# mcu.net
KiCad netlist of a schematic drawn in EAGLE
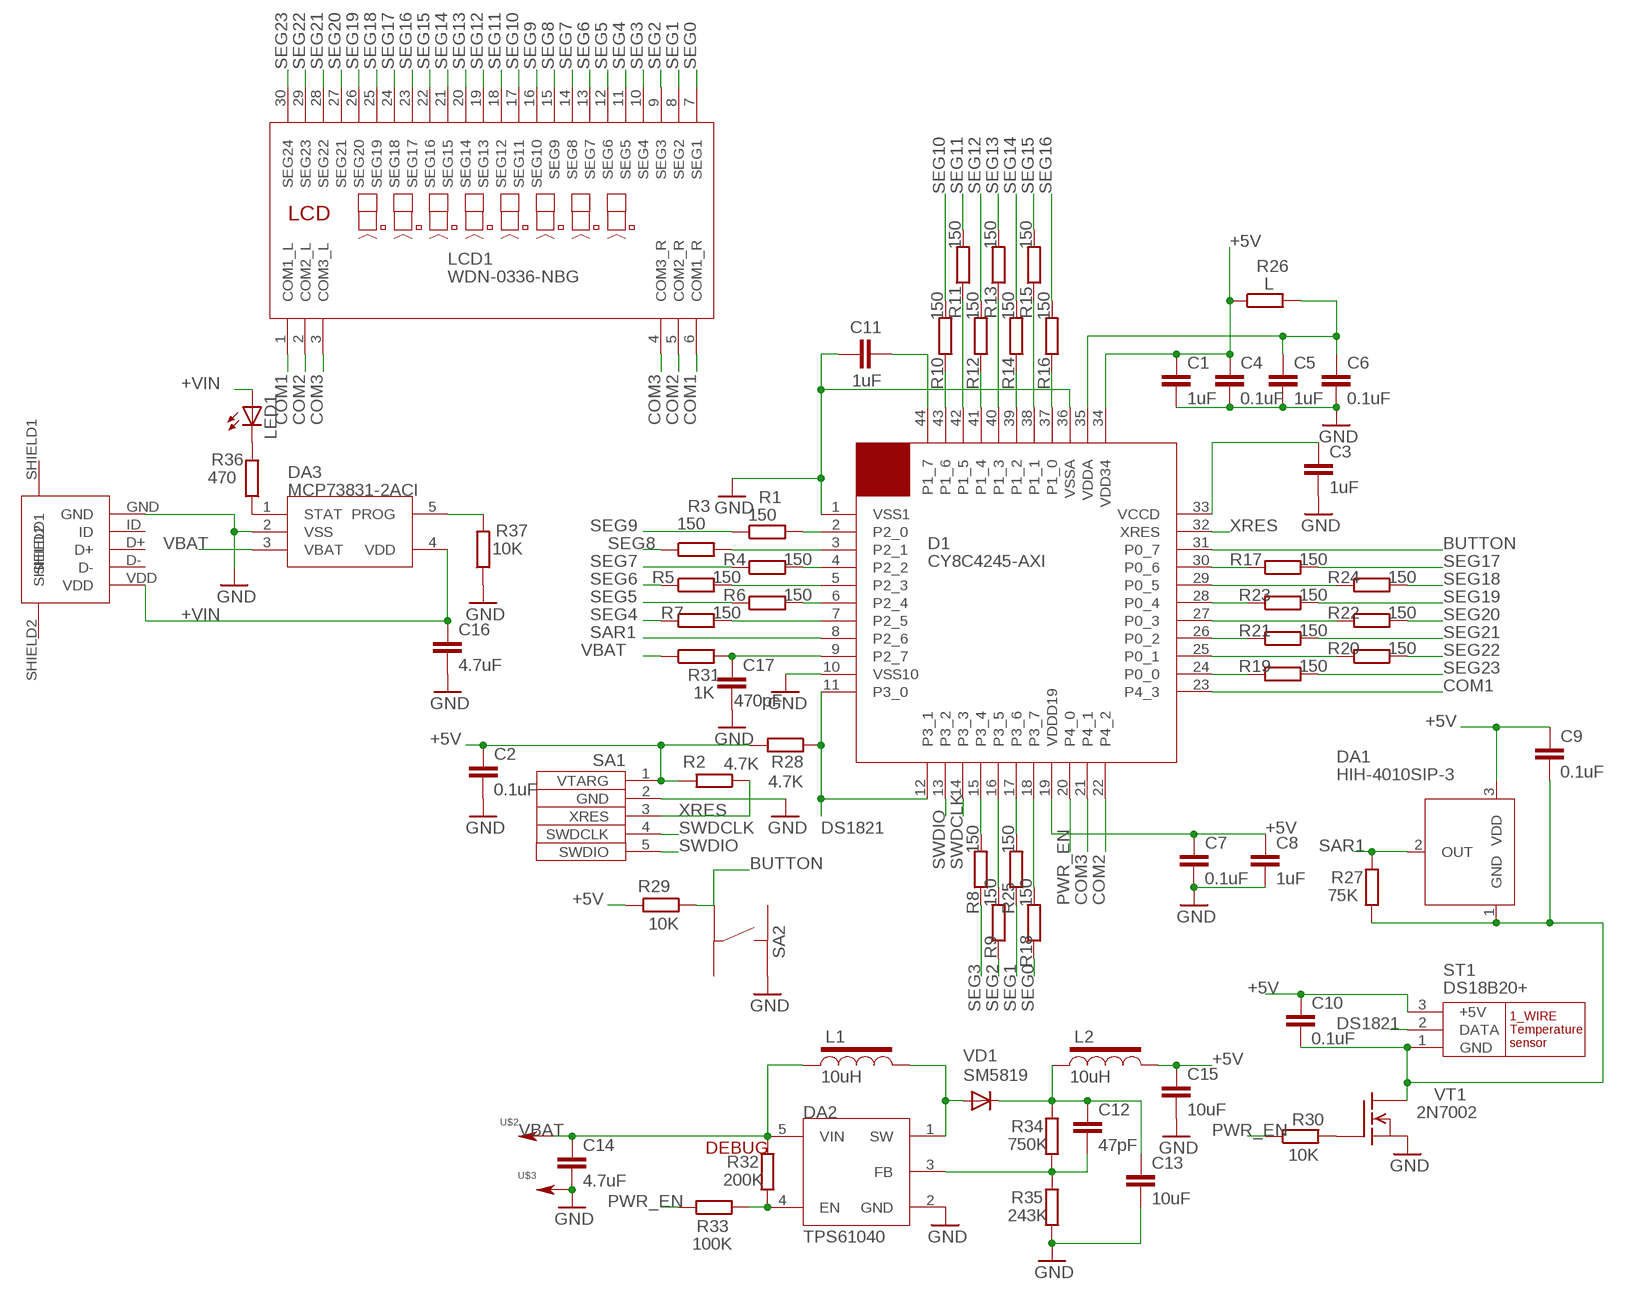
[diagram p0: schematic, sheet 1]

(export (version "E")
  (design (tool "Eeschema 10.0.6"))
  (components
    (comp (ref "C1")
      (value "1uF")
      (footprint "eagle-import:C0603")
      (libsource (lib "eagle-import") (part "C-EUC0603"))
    )
    (comp (ref "C2")
      (value "0.1uF")
      (footprint "eagle-import:C0603")
      (libsource (lib "eagle-import") (part "C-EUC0603"))
    )
    (comp (ref "C3")
      (value "1uF")
      (footprint "eagle-import:C0603")
      (libsource (lib "eagle-import") (part "C-EUC0603"))
    )
    (comp (ref "C4")
      (value "0.1uF")
      (footprint "eagle-import:C0603")
      (libsource (lib "eagle-import") (part "C-EUC0603"))
    )
    (comp (ref "C5")
      (value "1uF")
      (footprint "eagle-import:C0603")
      (libsource (lib "eagle-import") (part "C-EUC0603"))
    )
    (comp (ref "C6")
      (value "0.1uF")
      (footprint "eagle-import:C0603")
      (libsource (lib "eagle-import") (part "C-EUC0603"))
    )
    (comp (ref "C7")
      (value "0.1uF")
      (footprint "eagle-import:C0603")
      (libsource (lib "eagle-import") (part "C-EUC0603"))
    )
    (comp (ref "C8")
      (value "1uF")
      (footprint "eagle-import:C0603")
      (libsource (lib "eagle-import") (part "C-EUC0603"))
    )
    (comp (ref "C9")
      (value "0.1uF")
      (footprint "eagle-import:C0603")
      (libsource (lib "eagle-import") (part "C-EUC0603"))
    )
    (comp (ref "C10")
      (value "0.1uF")
      (footprint "eagle-import:C0603")
      (libsource (lib "eagle-import") (part "C-EUC0603"))
    )
    (comp (ref "C11")
      (value "1uF")
      (footprint "eagle-import:C0603")
      (libsource (lib "eagle-import") (part "C-EUC0603"))
    )
    (comp (ref "C12")
      (value "47pF")
      (footprint "eagle-import:C0805")
      (libsource (lib "eagle-import") (part "C-EUC0805"))
    )
    (comp (ref "C13")
      (value "10uF")
      (footprint "eagle-import:C0805")
      (libsource (lib "eagle-import") (part "C-EUC0805"))
    )
    (comp (ref "C14")
      (value "4.7uF")
      (footprint "eagle-import:C0805")
      (libsource (lib "eagle-import") (part "C-EUC0805"))
    )
    (comp (ref "C15")
      (value "10uF")
      (footprint "eagle-import:C0805")
      (libsource (lib "eagle-import") (part "C-EUC0805"))
    )
    (comp (ref "C16")
      (value "4.7uF")
      (footprint "eagle-import:C0805")
      (libsource (lib "eagle-import") (part "C-EUC0805"))
    )
    (comp (ref "C17")
      (value "470pF")
      (footprint "eagle-import:C0603")
      (libsource (lib "eagle-import") (part "C-EUC0603"))
    )
    (comp (ref "D1")
      (value "CY8C4245-AXI")
      (footprint "eagle-import:TQFP44")
      (libsource (lib "eagle-import") (part "CY8C4245-AXITQFP44"))
    )
    (comp (ref "DA1")
      (value "HIH-4010SIP-3")
      (footprint "eagle-import:SIP-3")
      (libsource (lib "eagle-import") (part "HIH-4010SIP-3"))
    )
    (comp (ref "DA2")
      (value "TPS61040")
      (footprint "eagle-import:SOT23-5L")
      (libsource (lib "eagle-import") (part "TPS61040"))
    )
    (comp (ref "DA3")
      (value "MCP73831-2ACI")
      (footprint "eagle-import:SOT23-5L")
      (libsource (lib "eagle-import") (part "MCP73831SOT23-5"))
    )
    (comp (ref "L1")
      (value "10uH")
      (footprint "eagle-import:SQC453226")
      (libsource (lib "eagle-import") (part "INDUCTOR453226"))
    )
    (comp (ref "L2")
      (value "10uH")
      (footprint "eagle-import:SQC453226")
      (libsource (lib "eagle-import") (part "INDUCTOR453226"))
    )
    (comp (ref "LCD1")
      (value "WDN-0336-NBG")
      (footprint "eagle-import:WDN0336")
      (libsource (lib "eagle-import") (part "WDN0336HOLE"))
    )
    (comp (ref "LED1")
      (value "LEDSMT1206")
      (footprint "eagle-import:1206")
      (libsource (lib "eagle-import") (part "LEDSMT1206"))
    )
    (comp (ref "R1")
      (value "150")
      (footprint "eagle-import:R0603")
      (libsource (lib "eagle-import") (part "R-EU_R0603"))
    )
    (comp (ref "R2")
      (value "4.7K")
      (footprint "eagle-import:R0603")
      (libsource (lib "eagle-import") (part "R-EU_R0603"))
    )
    (comp (ref "R3")
      (value "150")
      (footprint "eagle-import:R0603")
      (libsource (lib "eagle-import") (part "R-EU_R0603"))
    )
    (comp (ref "R4")
      (value "150")
      (footprint "eagle-import:R0603")
      (libsource (lib "eagle-import") (part "R-EU_R0603"))
    )
    (comp (ref "R5")
      (value "150")
      (footprint "eagle-import:R0603")
      (libsource (lib "eagle-import") (part "R-EU_R0603"))
    )
    (comp (ref "R6")
      (value "150")
      (footprint "eagle-import:R0603")
      (libsource (lib "eagle-import") (part "R-EU_R0603"))
    )
    (comp (ref "R7")
      (value "150")
      (footprint "eagle-import:R0603")
      (libsource (lib "eagle-import") (part "R-EU_R0603"))
    )
    (comp (ref "R8")
      (value "150")
      (footprint "eagle-import:R0603")
      (libsource (lib "eagle-import") (part "R-EU_R0603"))
    )
    (comp (ref "R9")
      (value "150")
      (footprint "eagle-import:R0603")
      (libsource (lib "eagle-import") (part "R-EU_R0603"))
    )
    (comp (ref "R10")
      (value "150")
      (footprint "eagle-import:R0603")
      (libsource (lib "eagle-import") (part "R-EU_R0603"))
    )
    (comp (ref "R11")
      (value "150")
      (footprint "eagle-import:R0603")
      (libsource (lib "eagle-import") (part "R-EU_R0603"))
    )
    (comp (ref "R12")
      (value "150")
      (footprint "eagle-import:R0603")
      (libsource (lib "eagle-import") (part "R-EU_R0603"))
    )
    (comp (ref "R13")
      (value "150")
      (footprint "eagle-import:R0603")
      (libsource (lib "eagle-import") (part "R-EU_R0603"))
    )
    (comp (ref "R14")
      (value "150")
      (footprint "eagle-import:R0603")
      (libsource (lib "eagle-import") (part "R-EU_R0603"))
    )
    (comp (ref "R15")
      (value "150")
      (footprint "eagle-import:R0603")
      (libsource (lib "eagle-import") (part "R-EU_R0603"))
    )
    (comp (ref "R16")
      (value "150")
      (footprint "eagle-import:R0603")
      (libsource (lib "eagle-import") (part "R-EU_R0603"))
    )
    (comp (ref "R17")
      (value "150")
      (footprint "eagle-import:R0603")
      (libsource (lib "eagle-import") (part "R-EU_R0603"))
    )
    (comp (ref "R18")
      (value "150")
      (footprint "eagle-import:R0603")
      (libsource (lib "eagle-import") (part "R-EU_R0603"))
    )
    (comp (ref "R19")
      (value "150")
      (footprint "eagle-import:R0603")
      (libsource (lib "eagle-import") (part "R-EU_R0603"))
    )
    (comp (ref "R20")
      (value "150")
      (footprint "eagle-import:R0603")
      (libsource (lib "eagle-import") (part "R-EU_R0603"))
    )
    (comp (ref "R21")
      (value "150")
      (footprint "eagle-import:R0603")
      (libsource (lib "eagle-import") (part "R-EU_R0603"))
    )
    (comp (ref "R22")
      (value "150")
      (footprint "eagle-import:R0603")
      (libsource (lib "eagle-import") (part "R-EU_R0603"))
    )
    (comp (ref "R23")
      (value "150")
      (footprint "eagle-import:R0603")
      (libsource (lib "eagle-import") (part "R-EU_R0603"))
    )
    (comp (ref "R24")
      (value "150")
      (footprint "eagle-import:R0603")
      (libsource (lib "eagle-import") (part "R-EU_R0603"))
    )
    (comp (ref "R25")
      (value "150")
      (footprint "eagle-import:R0603")
      (libsource (lib "eagle-import") (part "R-EU_R0603"))
    )
    (comp (ref "R26")
      (value "L")
      (footprint "eagle-import:R0805")
      (libsource (lib "eagle-import") (part "R-EU_R0805"))
    )
    (comp (ref "R27")
      (value "75K")
      (footprint "eagle-import:R0603")
      (libsource (lib "eagle-import") (part "R-EU_R0603"))
    )
    (comp (ref "R28")
      (value "4.7K")
      (footprint "eagle-import:R0603")
      (libsource (lib "eagle-import") (part "R-EU_R0603"))
    )
    (comp (ref "R29")
      (value "10K")
      (footprint "eagle-import:R0603")
      (libsource (lib "eagle-import") (part "R-EU_R0603"))
    )
    (comp (ref "R30")
      (value "10K")
      (footprint "eagle-import:R0603")
      (libsource (lib "eagle-import") (part "R-EU_R0603"))
    )
    (comp (ref "R31")
      (value "1K")
      (footprint "eagle-import:R0603")
      (libsource (lib "eagle-import") (part "R-EU_R0603"))
    )
    (comp (ref "R32")
      (value "200K")
      (footprint "eagle-import:R0603")
      (libsource (lib "eagle-import") (part "R-EU_R0603"))
    )
    (comp (ref "R33")
      (value "100K")
      (footprint "eagle-import:R0603")
      (libsource (lib "eagle-import") (part "R-EU_R0603"))
    )
    (comp (ref "R34")
      (value "750K")
      (footprint "eagle-import:R0805")
      (libsource (lib "eagle-import") (part "R-EU_R0805"))
    )
    (comp (ref "R35")
      (value "243K")
      (footprint "eagle-import:R0805")
      (libsource (lib "eagle-import") (part "R-EU_R0805"))
    )
    (comp (ref "R36")
      (value "470")
      (footprint "eagle-import:R1206")
      (libsource (lib "eagle-import") (part "R-EU_R1206"))
    )
    (comp (ref "R37")
      (value "10K")
      (footprint "eagle-import:R0603")
      (libsource (lib "eagle-import") (part "R-EU_R0603"))
    )
    (comp (ref "SA1")
      (value "SWDSWD-5")
      (footprint "eagle-import:SWD-5")
      (libsource (lib "eagle-import") (part "SWDSWD-5"))
    )
    (comp (ref "SA2")
      (value "TACKT_BUTTONIIT-1102S")
      (footprint "eagle-import:IIT-1102S")
      (libsource (lib "eagle-import") (part "TACKT_BUTTONIIT-1102S"))
    )
    (comp (ref "ST1")
      (value "DS18B20+")
      (footprint "eagle-import:TO92-")
      (libsource (lib "eagle-import") (part "DS18B20TO92"))
    )
    (comp (ref "U$1")
      (value "USB-MICRO")
      (footprint "eagle-import:USB-MICRO-SMD")
      (libsource (lib "eagle-import") (part "USB-MICRO"))
    )
    (comp (ref "U$2")
      (value "1-PINHOME")
      (footprint "eagle-import:1-PIN_HOME")
      (libsource (lib "eagle-import") (part "1-PINHOME"))
    )
    (comp (ref "U$3")
      (value "1-PIN2_54")
      (footprint "eagle-import:1_PIN_2_54")
      (libsource (lib "eagle-import") (part "1-PIN2_54"))
    )
    (comp (ref "VD1")
      (value "SM5819")
      (footprint "eagle-import:MELF-MLL41")
      (libsource (lib "eagle-import") (part "SM5819MELF"))
    )
    (comp (ref "VT1")
      (value "2N7002")
      (footprint "eagle-import:SOT23")
      (libsource (lib "eagle-import") (part "2N7002"))
    )
  )
  (nets
    (net (code "1") (name "/+5V") (class "Default")
      (node (ref "C1") (pin "1") (pinfunction "1_1") (pintype "passive"))
      (node (ref "C10") (pin "1") (pinfunction "1_1") (pintype "passive"))
      (node (ref "C15") (pin "1") (pinfunction "1_1") (pintype "passive"))
      (node (ref "C2") (pin "1") (pinfunction "1_1") (pintype "passive"))
      (node (ref "C4") (pin "1") (pinfunction "1_1") (pintype "passive"))
      (node (ref "C7") (pin "1") (pinfunction "1_1") (pintype "passive"))
      (node (ref "C8") (pin "1") (pinfunction "1_1") (pintype "passive"))
      (node (ref "C9") (pin "1") (pinfunction "1_1") (pintype "passive"))
      (node (ref "D1") (pin "19") (pinfunction "VDDD19_19") (pintype "power_in"))
      (node (ref "D1") (pin "34") (pinfunction "VDD34_34") (pintype "power_in"))
      (node (ref "DA1") (pin "3") (pinfunction "VDD_3") (pintype "power_in"))
      (node (ref "L2") (pin "2") (pinfunction "L2_2") (pintype "passive"))
      (node (ref "R2") (pin "2") (pinfunction "2_2") (pintype "passive"))
      (node (ref "R26") (pin "1") (pinfunction "1_1") (pintype "passive"))
      (node (ref "R28") (pin "2") (pinfunction "2_2") (pintype "passive"))
      (node (ref "R29") (pin "2") (pinfunction "2_2") (pintype "passive"))
      (node (ref "SA1") (pin "1") (pinfunction "VTARG_1") (pintype "bidirectional"))
      (node (ref "ST1") (pin "3") (pinfunction "+5V_3") (pintype "power_in"))
    )
    (net (code "2") (name "/+VIN") (class "Default")
      (node (ref "C16") (pin "1") (pinfunction "1_1") (pintype "passive"))
      (node (ref "DA3") (pin "4") (pinfunction "VDD_4") (pintype "power_in"))
      (node (ref "LED1") (pin "A") (pinfunction "A_A") (pintype "passive"))
      (node (ref "U$1") (pin "VDD") (pinfunction "VDD_VDD") (pintype "power_in"))
    )
    (net (code "3") (name "/BUTTON") (class "Default")
      (node (ref "D1") (pin "31") (pinfunction "P0_7_31") (pintype "bidirectional"))
      (node (ref "R29") (pin "1") (pinfunction "1_1") (pintype "passive"))
      (node (ref "SA2") (pin "SSR") (pinfunction "2_SSR") (pintype "passive"))
    )
    (net (code "4") (name "/COM1") (class "Default")
      (node (ref "D1") (pin "23") (pinfunction "P4_3_23") (pintype "bidirectional"))
      (node (ref "LCD1") (pin "1") (pinfunction "COM1_L_1") (pintype "input"))
      (node (ref "LCD1") (pin "6") (pinfunction "COM1_R_6") (pintype "input"))
    )
    (net (code "5") (name "/COM2") (class "Default")
      (node (ref "D1") (pin "22") (pinfunction "P4_2_22") (pintype "bidirectional"))
      (node (ref "LCD1") (pin "2") (pinfunction "COM2_L_2") (pintype "input"))
      (node (ref "LCD1") (pin "5") (pinfunction "COM2_R_5") (pintype "input"))
    )
    (net (code "6") (name "/COM3") (class "Default")
      (node (ref "D1") (pin "21") (pinfunction "P4_1_21") (pintype "bidirectional"))
      (node (ref "LCD1") (pin "3") (pinfunction "COM3_L_3") (pintype "input"))
      (node (ref "LCD1") (pin "4") (pinfunction "COM3_R_4") (pintype "input"))
    )
    (net (code "7") (name "/DS1821") (class "Default")
      (node (ref "D1") (pin "11") (pinfunction "P3_0_11") (pintype "bidirectional"))
      (node (ref "D1") (pin "12") (pinfunction "P3_1_12") (pintype "bidirectional"))
      (node (ref "R28") (pin "1") (pinfunction "1_1") (pintype "passive"))
      (node (ref "ST1") (pin "2") (pinfunction "DATA_2") (pintype "bidirectional"))
    )
    (net (code "8") (name "/PWR_EN") (class "Default")
      (node (ref "D1") (pin "20") (pinfunction "P4_0_20") (pintype "bidirectional"))
      (node (ref "R30") (pin "1") (pinfunction "1_1") (pintype "passive"))
      (node (ref "R33") (pin "1") (pinfunction "1_1") (pintype "passive"))
    )
    (net (code "9") (name "/SAR1") (class "Default")
      (node (ref "D1") (pin "8") (pinfunction "P2_6_8") (pintype "bidirectional"))
      (node (ref "DA1") (pin "2") (pinfunction "OUT_2") (pintype "power_in"))
      (node (ref "R27") (pin "2") (pinfunction "2_2") (pintype "passive"))
    )
    (net (code "10") (name "/SEG0") (class "Default")
      (node (ref "LCD1") (pin "7") (pinfunction "SEG1_7") (pintype "input"))
      (node (ref "R18") (pin "1") (pinfunction "1_1") (pintype "passive"))
    )
    (net (code "11") (name "/SEG1") (class "Default")
      (node (ref "LCD1") (pin "8") (pinfunction "SEG2_8") (pintype "input"))
      (node (ref "R25") (pin "1") (pinfunction "1_1") (pintype "passive"))
    )
    (net (code "12") (name "/SEG2") (class "Default")
      (node (ref "LCD1") (pin "9") (pinfunction "SEG3_9") (pintype "input"))
      (node (ref "R9") (pin "1") (pinfunction "1_1") (pintype "passive"))
    )
    (net (code "13") (name "/SEG3") (class "Default")
      (node (ref "LCD1") (pin "10") (pinfunction "SEG4_10") (pintype "input"))
      (node (ref "R8") (pin "1") (pinfunction "1_1") (pintype "passive"))
    )
    (net (code "14") (name "/SEG4") (class "Default")
      (node (ref "LCD1") (pin "11") (pinfunction "SEG5_11") (pintype "input"))
      (node (ref "R7") (pin "1") (pinfunction "1_1") (pintype "passive"))
    )
    (net (code "15") (name "/SEG5") (class "Default")
      (node (ref "LCD1") (pin "12") (pinfunction "SEG6_12") (pintype "input"))
      (node (ref "R6") (pin "1") (pinfunction "1_1") (pintype "passive"))
    )
    (net (code "16") (name "/SEG6") (class "Default")
      (node (ref "LCD1") (pin "13") (pinfunction "SEG7_13") (pintype "input"))
      (node (ref "R5") (pin "1") (pinfunction "1_1") (pintype "passive"))
    )
    (net (code "17") (name "/SEG7") (class "Default")
      (node (ref "LCD1") (pin "14") (pinfunction "SEG8_14") (pintype "input"))
      (node (ref "R4") (pin "1") (pinfunction "1_1") (pintype "passive"))
    )
    (net (code "18") (name "/SEG8") (class "Default")
      (node (ref "LCD1") (pin "15") (pinfunction "SEG9_15") (pintype "input"))
      (node (ref "R3") (pin "1") (pinfunction "1_1") (pintype "passive"))
    )
    (net (code "19") (name "/SEG9") (class "Default")
      (node (ref "LCD1") (pin "16") (pinfunction "SEG10_16") (pintype "input"))
      (node (ref "R1") (pin "1") (pinfunction "1_1") (pintype "passive"))
    )
    (net (code "20") (name "/SEG10") (class "Default")
      (node (ref "LCD1") (pin "17") (pinfunction "SEG11_17") (pintype "input"))
      (node (ref "R10") (pin "2") (pinfunction "2_2") (pintype "passive"))
    )
    (net (code "21") (name "/SEG11") (class "Default")
      (node (ref "LCD1") (pin "18") (pinfunction "SEG12_18") (pintype "input"))
      (node (ref "R11") (pin "2") (pinfunction "2_2") (pintype "passive"))
    )
    (net (code "22") (name "/SEG12") (class "Default")
      (node (ref "LCD1") (pin "19") (pinfunction "SEG13_19") (pintype "input"))
      (node (ref "R12") (pin "2") (pinfunction "2_2") (pintype "passive"))
    )
    (net (code "23") (name "/SEG13") (class "Default")
      (node (ref "LCD1") (pin "20") (pinfunction "SEG14_20") (pintype "input"))
      (node (ref "R13") (pin "2") (pinfunction "2_2") (pintype "passive"))
    )
    (net (code "24") (name "/SEG14") (class "Default")
      (node (ref "LCD1") (pin "21") (pinfunction "SEG15_21") (pintype "input"))
      (node (ref "R14") (pin "2") (pinfunction "2_2") (pintype "passive"))
    )
    (net (code "25") (name "/SEG15") (class "Default")
      (node (ref "LCD1") (pin "22") (pinfunction "SEG16_22") (pintype "input"))
      (node (ref "R15") (pin "2") (pinfunction "2_2") (pintype "passive"))
    )
    (net (code "26") (name "/SEG16") (class "Default")
      (node (ref "LCD1") (pin "23") (pinfunction "SEG17_23") (pintype "input"))
      (node (ref "R16") (pin "2") (pinfunction "2_2") (pintype "passive"))
    )
    (net (code "27") (name "/SEG17") (class "Default")
      (node (ref "LCD1") (pin "24") (pinfunction "SEG18_24") (pintype "input"))
      (node (ref "R17") (pin "2") (pinfunction "2_2") (pintype "passive"))
    )
    (net (code "28") (name "/SEG18") (class "Default")
      (node (ref "LCD1") (pin "25") (pinfunction "SEG19_25") (pintype "input"))
      (node (ref "R24") (pin "2") (pinfunction "2_2") (pintype "passive"))
    )
    (net (code "29") (name "/SEG19") (class "Default")
      (node (ref "LCD1") (pin "26") (pinfunction "SEG20_26") (pintype "input"))
      (node (ref "R23") (pin "2") (pinfunction "2_2") (pintype "passive"))
    )
    (net (code "30") (name "/SEG20") (class "Default")
      (node (ref "LCD1") (pin "27") (pinfunction "SEG21_27") (pintype "input"))
      (node (ref "R22") (pin "2") (pinfunction "2_2") (pintype "passive"))
    )
    (net (code "31") (name "/SEG21") (class "Default")
      (node (ref "LCD1") (pin "28") (pinfunction "SEG22_28") (pintype "input"))
      (node (ref "R21") (pin "2") (pinfunction "2_2") (pintype "passive"))
    )
    (net (code "32") (name "/SEG22") (class "Default")
      (node (ref "LCD1") (pin "29") (pinfunction "SEG23_29") (pintype "input"))
      (node (ref "R20") (pin "2") (pinfunction "2_2") (pintype "passive"))
    )
    (net (code "33") (name "/SEG23") (class "Default")
      (node (ref "LCD1") (pin "30") (pinfunction "SEG24_30") (pintype "input"))
      (node (ref "R19") (pin "2") (pinfunction "2_2") (pintype "passive"))
    )
    (net (code "34") (name "/SWDCLK") (class "Default")
      (node (ref "D1") (pin "14") (pinfunction "P3_3_14") (pintype "bidirectional"))
      (node (ref "SA1") (pin "4") (pinfunction "SWDCLK_4") (pintype "bidirectional"))
    )
    (net (code "35") (name "/SWDIO") (class "Default")
      (node (ref "D1") (pin "13") (pinfunction "P3_2_13") (pintype "bidirectional"))
      (node (ref "SA1") (pin "5") (pinfunction "SWDIO_5") (pintype "bidirectional"))
    )
    (net (code "36") (name "/VBAT") (class "Default")
      (node (ref "C14") (pin "1") (pinfunction "1_1") (pintype "passive"))
      (node (ref "DA2") (pin "5") (pinfunction "VIN_5") (pintype "power_in"))
      (node (ref "DA3") (pin "3") (pinfunction "VBAT_3") (pintype "passive"))
      (node (ref "L1") (pin "1") (pinfunction "L1_1") (pintype "passive"))
      (node (ref "R31") (pin "1") (pinfunction "1_1") (pintype "passive"))
      (node (ref "R32") (pin "2") (pinfunction "2_2") (pintype "passive"))
      (node (ref "U$2") (pin "P$1") (pinfunction "S_P$1") (pintype "passive"))
    )
    (net (code "37") (name "/XRES") (class "Default")
      (node (ref "D1") (pin "32") (pinfunction "XRES_32") (pintype "input"))
      (node (ref "R2") (pin "1") (pinfunction "1_1") (pintype "passive"))
      (node (ref "SA1") (pin "3") (pinfunction "XRES_3") (pintype "bidirectional"))
    )
    (net (code "38") (name "GND") (class "Default")
      (node (ref "C1") (pin "2") (pinfunction "2_2") (pintype "passive"))
      (node (ref "C11") (pin "1") (pinfunction "1_1") (pintype "passive"))
      (node (ref "C13") (pin "2") (pinfunction "2_2") (pintype "passive"))
      (node (ref "C14") (pin "2") (pinfunction "2_2") (pintype "passive"))
      (node (ref "C15") (pin "2") (pinfunction "2_2") (pintype "passive"))
      (node (ref "C16") (pin "2") (pinfunction "2_2") (pintype "passive"))
      (node (ref "C17") (pin "2") (pinfunction "2_2") (pintype "passive"))
      (node (ref "C2") (pin "2") (pinfunction "2_2") (pintype "passive"))
      (node (ref "C3") (pin "2") (pinfunction "2_2") (pintype "passive"))
      (node (ref "C4") (pin "2") (pinfunction "2_2") (pintype "passive"))
      (node (ref "C5") (pin "2") (pinfunction "2_2") (pintype "passive"))
      (node (ref "C6") (pin "2") (pinfunction "2_2") (pintype "passive"))
      (node (ref "C7") (pin "2") (pinfunction "2_2") (pintype "passive"))
      (node (ref "C8") (pin "2") (pinfunction "2_2") (pintype "passive"))
      (node (ref "D1") (pin "1") (pinfunction "VSS1_1") (pintype "power_in"))
      (node (ref "D1") (pin "10") (pinfunction "VSS10_10") (pintype "power_in"))
      (node (ref "D1") (pin "36") (pinfunction "VSSA_36") (pintype "power_in"))
      (node (ref "DA2") (pin "2") (pinfunction "GND_2") (pintype "power_in"))
      (node (ref "DA3") (pin "2") (pinfunction "VSS_2") (pintype "power_in"))
      (node (ref "R35") (pin "1") (pinfunction "1_1") (pintype "passive"))
      (node (ref "R37") (pin "1") (pinfunction "1_1") (pintype "passive"))
      (node (ref "SA1") (pin "2") (pinfunction "GND_2") (pintype "bidirectional"))
      (node (ref "SA2") (pin "SL") (pinfunction "3_SL") (pintype "passive"))
      (node (ref "U$1") (pin "GND") (pinfunction "GND_GND") (pintype "power_in"))
      (node (ref "U$3") (pin "P$1") (pinfunction "S_P$1") (pintype "passive"))
      (node (ref "VT1") (pin "2") (pinfunction "S_2") (pintype "passive"))
    )
    (net (code "39") (name "Net-(D1-P0_0)") (class "Default")
      (node (ref "D1") (pin "24") (pinfunction "P0_0_24") (pintype "bidirectional"))
      (node (ref "R19") (pin "1") (pinfunction "1_1") (pintype "passive"))
    )
    (net (code "40") (name "Net-(D1-P0_1)") (class "Default")
      (node (ref "D1") (pin "25") (pinfunction "P0_1_25") (pintype "bidirectional"))
      (node (ref "R20") (pin "1") (pinfunction "1_1") (pintype "passive"))
    )
    (net (code "41") (name "Net-(D1-P0_2)") (class "Default")
      (node (ref "D1") (pin "26") (pinfunction "P0_2_26") (pintype "bidirectional"))
      (node (ref "R21") (pin "1") (pinfunction "1_1") (pintype "passive"))
    )
    (net (code "42") (name "Net-(D1-P0_3)") (class "Default")
      (node (ref "D1") (pin "27") (pinfunction "P0_3_27") (pintype "bidirectional"))
      (node (ref "R22") (pin "1") (pinfunction "1_1") (pintype "passive"))
    )
    (net (code "43") (name "Net-(D1-P0_4)") (class "Default")
      (node (ref "D1") (pin "28") (pinfunction "P0_4_28") (pintype "bidirectional"))
      (node (ref "R23") (pin "1") (pinfunction "1_1") (pintype "passive"))
    )
    (net (code "44") (name "Net-(D1-P0_5)") (class "Default")
      (node (ref "D1") (pin "29") (pinfunction "P0_5_29") (pintype "bidirectional"))
      (node (ref "R24") (pin "1") (pinfunction "1_1") (pintype "passive"))
    )
    (net (code "45") (name "Net-(D1-P0_6)") (class "Default")
      (node (ref "D1") (pin "30") (pinfunction "P0_6_30") (pintype "bidirectional"))
      (node (ref "R17") (pin "1") (pinfunction "1_1") (pintype "passive"))
    )
    (net (code "46") (name "Net-(D1-P1_0)") (class "Default")
      (node (ref "D1") (pin "37") (pinfunction "P1_0_37") (pintype "bidirectional"))
      (node (ref "R16") (pin "1") (pinfunction "1_1") (pintype "passive"))
    )
    (net (code "47") (name "Net-(D1-P1_1)") (class "Default")
      (node (ref "D1") (pin "38") (pinfunction "P1_1_38") (pintype "bidirectional"))
      (node (ref "R15") (pin "1") (pinfunction "1_1") (pintype "passive"))
    )
    (net (code "48") (name "Net-(D1-P1_2)") (class "Default")
      (node (ref "D1") (pin "39") (pinfunction "P1_2_39") (pintype "bidirectional"))
      (node (ref "R14") (pin "1") (pinfunction "1_1") (pintype "passive"))
    )
    (net (code "49") (name "Net-(D1-P1_3)") (class "Default")
      (node (ref "D1") (pin "40") (pinfunction "P1_3_40") (pintype "bidirectional"))
      (node (ref "R13") (pin "1") (pinfunction "1_1") (pintype "passive"))
    )
    (net (code "50") (name "Net-(D1-P1_4)") (class "Default")
      (node (ref "D1") (pin "41") (pinfunction "P1_4_41") (pintype "bidirectional"))
      (node (ref "R12") (pin "1") (pinfunction "1_1") (pintype "passive"))
    )
    (net (code "51") (name "Net-(D1-P1_5)") (class "Default")
      (node (ref "D1") (pin "42") (pinfunction "P1_5_42") (pintype "bidirectional"))
      (node (ref "R11") (pin "1") (pinfunction "1_1") (pintype "passive"))
    )
    (net (code "52") (name "Net-(D1-P1_6)") (class "Default")
      (node (ref "D1") (pin "43") (pinfunction "P1_6_43") (pintype "bidirectional"))
      (node (ref "R10") (pin "1") (pinfunction "1_1") (pintype "passive"))
    )
    (net (code "53") (name "Net-(D1-P1_7)") (class "Default")
      (node (ref "C11") (pin "2") (pinfunction "2_2") (pintype "passive"))
      (node (ref "D1") (pin "44") (pinfunction "P1_7_44") (pintype "bidirectional"))
    )
    (net (code "54") (name "Net-(D1-P2_0)") (class "Default")
      (node (ref "D1") (pin "2") (pinfunction "P2_0_2") (pintype "bidirectional"))
      (node (ref "R1") (pin "2") (pinfunction "2_2") (pintype "passive"))
    )
    (net (code "55") (name "Net-(D1-P2_1)") (class "Default")
      (node (ref "D1") (pin "3") (pinfunction "P2_1_3") (pintype "bidirectional"))
      (node (ref "R3") (pin "2") (pinfunction "2_2") (pintype "passive"))
    )
    (net (code "56") (name "Net-(D1-P2_2)") (class "Default")
      (node (ref "D1") (pin "4") (pinfunction "P2_2_4") (pintype "bidirectional"))
      (node (ref "R4") (pin "2") (pinfunction "2_2") (pintype "passive"))
    )
    (net (code "57") (name "Net-(D1-P2_3)") (class "Default")
      (node (ref "D1") (pin "5") (pinfunction "P2_3_5") (pintype "bidirectional"))
      (node (ref "R5") (pin "2") (pinfunction "2_2") (pintype "passive"))
    )
    (net (code "58") (name "Net-(D1-P2_4)") (class "Default")
      (node (ref "D1") (pin "6") (pinfunction "P2_4_6") (pintype "bidirectional"))
      (node (ref "R6") (pin "2") (pinfunction "2_2") (pintype "passive"))
    )
    (net (code "59") (name "Net-(D1-P2_5)") (class "Default")
      (node (ref "D1") (pin "7") (pinfunction "P2_5_7") (pintype "bidirectional"))
      (node (ref "R7") (pin "2") (pinfunction "2_2") (pintype "passive"))
    )
    (net (code "60") (name "Net-(D1-P2_7)") (class "Default")
      (node (ref "C17") (pin "1") (pinfunction "1_1") (pintype "passive"))
      (node (ref "D1") (pin "9") (pinfunction "P2_7_9") (pintype "bidirectional"))
      (node (ref "R31") (pin "2") (pinfunction "2_2") (pintype "passive"))
    )
    (net (code "61") (name "Net-(D1-P3_4)") (class "Default")
      (node (ref "D1") (pin "15") (pinfunction "P3_4_15") (pintype "bidirectional"))
      (node (ref "R8") (pin "2") (pinfunction "2_2") (pintype "passive"))
    )
    (net (code "62") (name "Net-(D1-P3_5)") (class "Default")
      (node (ref "D1") (pin "16") (pinfunction "P3_5_16") (pintype "bidirectional"))
      (node (ref "R9") (pin "2") (pinfunction "2_2") (pintype "passive"))
    )
    (net (code "63") (name "Net-(D1-P3_6)") (class "Default")
      (node (ref "D1") (pin "17") (pinfunction "P3_6_17") (pintype "bidirectional"))
      (node (ref "R25") (pin "2") (pinfunction "2_2") (pintype "passive"))
    )
    (net (code "64") (name "Net-(D1-P3_7)") (class "Default")
      (node (ref "D1") (pin "18") (pinfunction "P3_7_18") (pintype "bidirectional"))
      (node (ref "R18") (pin "2") (pinfunction "2_2") (pintype "passive"))
    )
    (net (code "65") (name "Net-(D1-VCCD)") (class "Default")
      (node (ref "C3") (pin "1") (pinfunction "1_1") (pintype "passive"))
      (node (ref "D1") (pin "33") (pinfunction "VCCD_33") (pintype "power_in"))
    )
    (net (code "66") (name "Net-(D1-VDDA)") (class "Default")
      (node (ref "C5") (pin "1") (pinfunction "1_1") (pintype "passive"))
      (node (ref "C6") (pin "1") (pinfunction "1_1") (pintype "passive"))
      (node (ref "D1") (pin "35") (pinfunction "VDDA_35") (pintype "power_in"))
      (node (ref "R26") (pin "2") (pinfunction "2_2") (pintype "passive"))
    )
    (net (code "67") (name "Net-(DA1-GND)") (class "Default")
      (node (ref "C10") (pin "2") (pinfunction "2_2") (pintype "passive"))
      (node (ref "C9") (pin "2") (pinfunction "2_2") (pintype "passive"))
      (node (ref "DA1") (pin "1") (pinfunction "GND_1") (pintype "power_in"))
      (node (ref "R27") (pin "1") (pinfunction "1_1") (pintype "passive"))
      (node (ref "ST1") (pin "1") (pinfunction "GND_1") (pintype "power_in"))
      (node (ref "VT1") (pin "3") (pinfunction "D_3") (pintype "passive"))
    )
    (net (code "68") (name "Net-(DA2-EN)") (class "Default")
      (node (ref "DA2") (pin "4") (pinfunction "EN_4") (pintype "input"))
      (node (ref "R32") (pin "1") (pinfunction "1_1") (pintype "passive"))
      (node (ref "R33") (pin "2") (pinfunction "2_2") (pintype "passive"))
    )
    (net (code "69") (name "Net-(DA2-FB)") (class "Default")
      (node (ref "C12") (pin "2") (pinfunction "2_2") (pintype "passive"))
      (node (ref "DA2") (pin "3") (pinfunction "FB_3") (pintype "input"))
      (node (ref "R34") (pin "1") (pinfunction "1_1") (pintype "passive"))
      (node (ref "R35") (pin "2") (pinfunction "2_2") (pintype "passive"))
    )
    (net (code "70") (name "Net-(DA2-SW)") (class "Default")
      (node (ref "DA2") (pin "1") (pinfunction "SW_1") (pintype "output"))
      (node (ref "L1") (pin "2") (pinfunction "L2_2") (pintype "passive"))
      (node (ref "VD1") (pin "A") (pinfunction "A_A") (pintype "passive"))
    )
    (net (code "71") (name "Net-(DA3-PROG)") (class "Default")
      (node (ref "DA3") (pin "5") (pinfunction "PROG_5") (pintype "passive"))
      (node (ref "R37") (pin "2") (pinfunction "2_2") (pintype "passive"))
    )
    (net (code "72") (name "Net-(DA3-STAT)") (class "Default")
      (node (ref "DA3") (pin "1") (pinfunction "STAT_1") (pintype "output"))
      (node (ref "R36") (pin "1") (pinfunction "1_1") (pintype "passive"))
    )
    (net (code "73") (name "Net-(L2-L1)") (class "Default")
      (node (ref "C12") (pin "1") (pinfunction "1_1") (pintype "passive"))
      (node (ref "C13") (pin "1") (pinfunction "1_1") (pintype "passive"))
      (node (ref "L2") (pin "1") (pinfunction "L1_1") (pintype "passive"))
      (node (ref "R34") (pin "2") (pinfunction "2_2") (pintype "passive"))
      (node (ref "VD1") (pin "C") (pinfunction "C_C") (pintype "passive"))
    )
    (net (code "74") (name "Net-(LED1-PadC)") (class "Default")
      (node (ref "LED1") (pin "C") (pinfunction "C_C") (pintype "passive"))
      (node (ref "R36") (pin "2") (pinfunction "2_2") (pintype "passive"))
    )
    (net (code "75") (name "Net-(VT1-G)") (class "Default")
      (node (ref "R30") (pin "2") (pinfunction "2_2") (pintype "passive"))
      (node (ref "VT1") (pin "1") (pinfunction "G_1") (pintype "passive"))
    )
    (net (code "76") (name "unconnected-(SA2-1-PadSSL)") (class "Default")
      (node (ref "SA2") (pin "SSL") (pinfunction "1_SSL") (pintype "passive"))
    )
    (net (code "77") (name "unconnected-(SA2-4-PadSR)") (class "Default")
      (node (ref "SA2") (pin "SR") (pinfunction "4_SR") (pintype "passive"))
    )
    (net (code "78") (name "unconnected-(U$1-PadD+)") (class "Default")
      (node (ref "U$1") (pin "D+") (pinfunction "D+_D+") (pintype "bidirectional"))
    )
    (net (code "79") (name "unconnected-(U$1-PadD-)") (class "Default")
      (node (ref "U$1") (pin "D-") (pinfunction "D-_D-") (pintype "bidirectional"))
    )
    (net (code "80") (name "unconnected-(U$1-PadID)") (class "Default")
      (node (ref "U$1") (pin "ID") (pinfunction "ID_ID") (pintype "bidirectional"))
    )
    (net (code "81") (name "unconnected-(U$1-PadSHIELD1)") (class "Default")
      (node (ref "U$1") (pin "SHIELD1") (pinfunction "SHIELD1_SHIELD1") (pintype "passive"))
    )
    (net (code "82") (name "unconnected-(U$1-PadSHIELD2)") (class "Default")
      (node (ref "U$1") (pin "SHIELD2") (pinfunction "SHIELD2_SHIELD2") (pintype "passive"))
    )
  )
)
